# STM32L412CBU6.net
KiCad netlist of a schematic drawn in Altium Designer
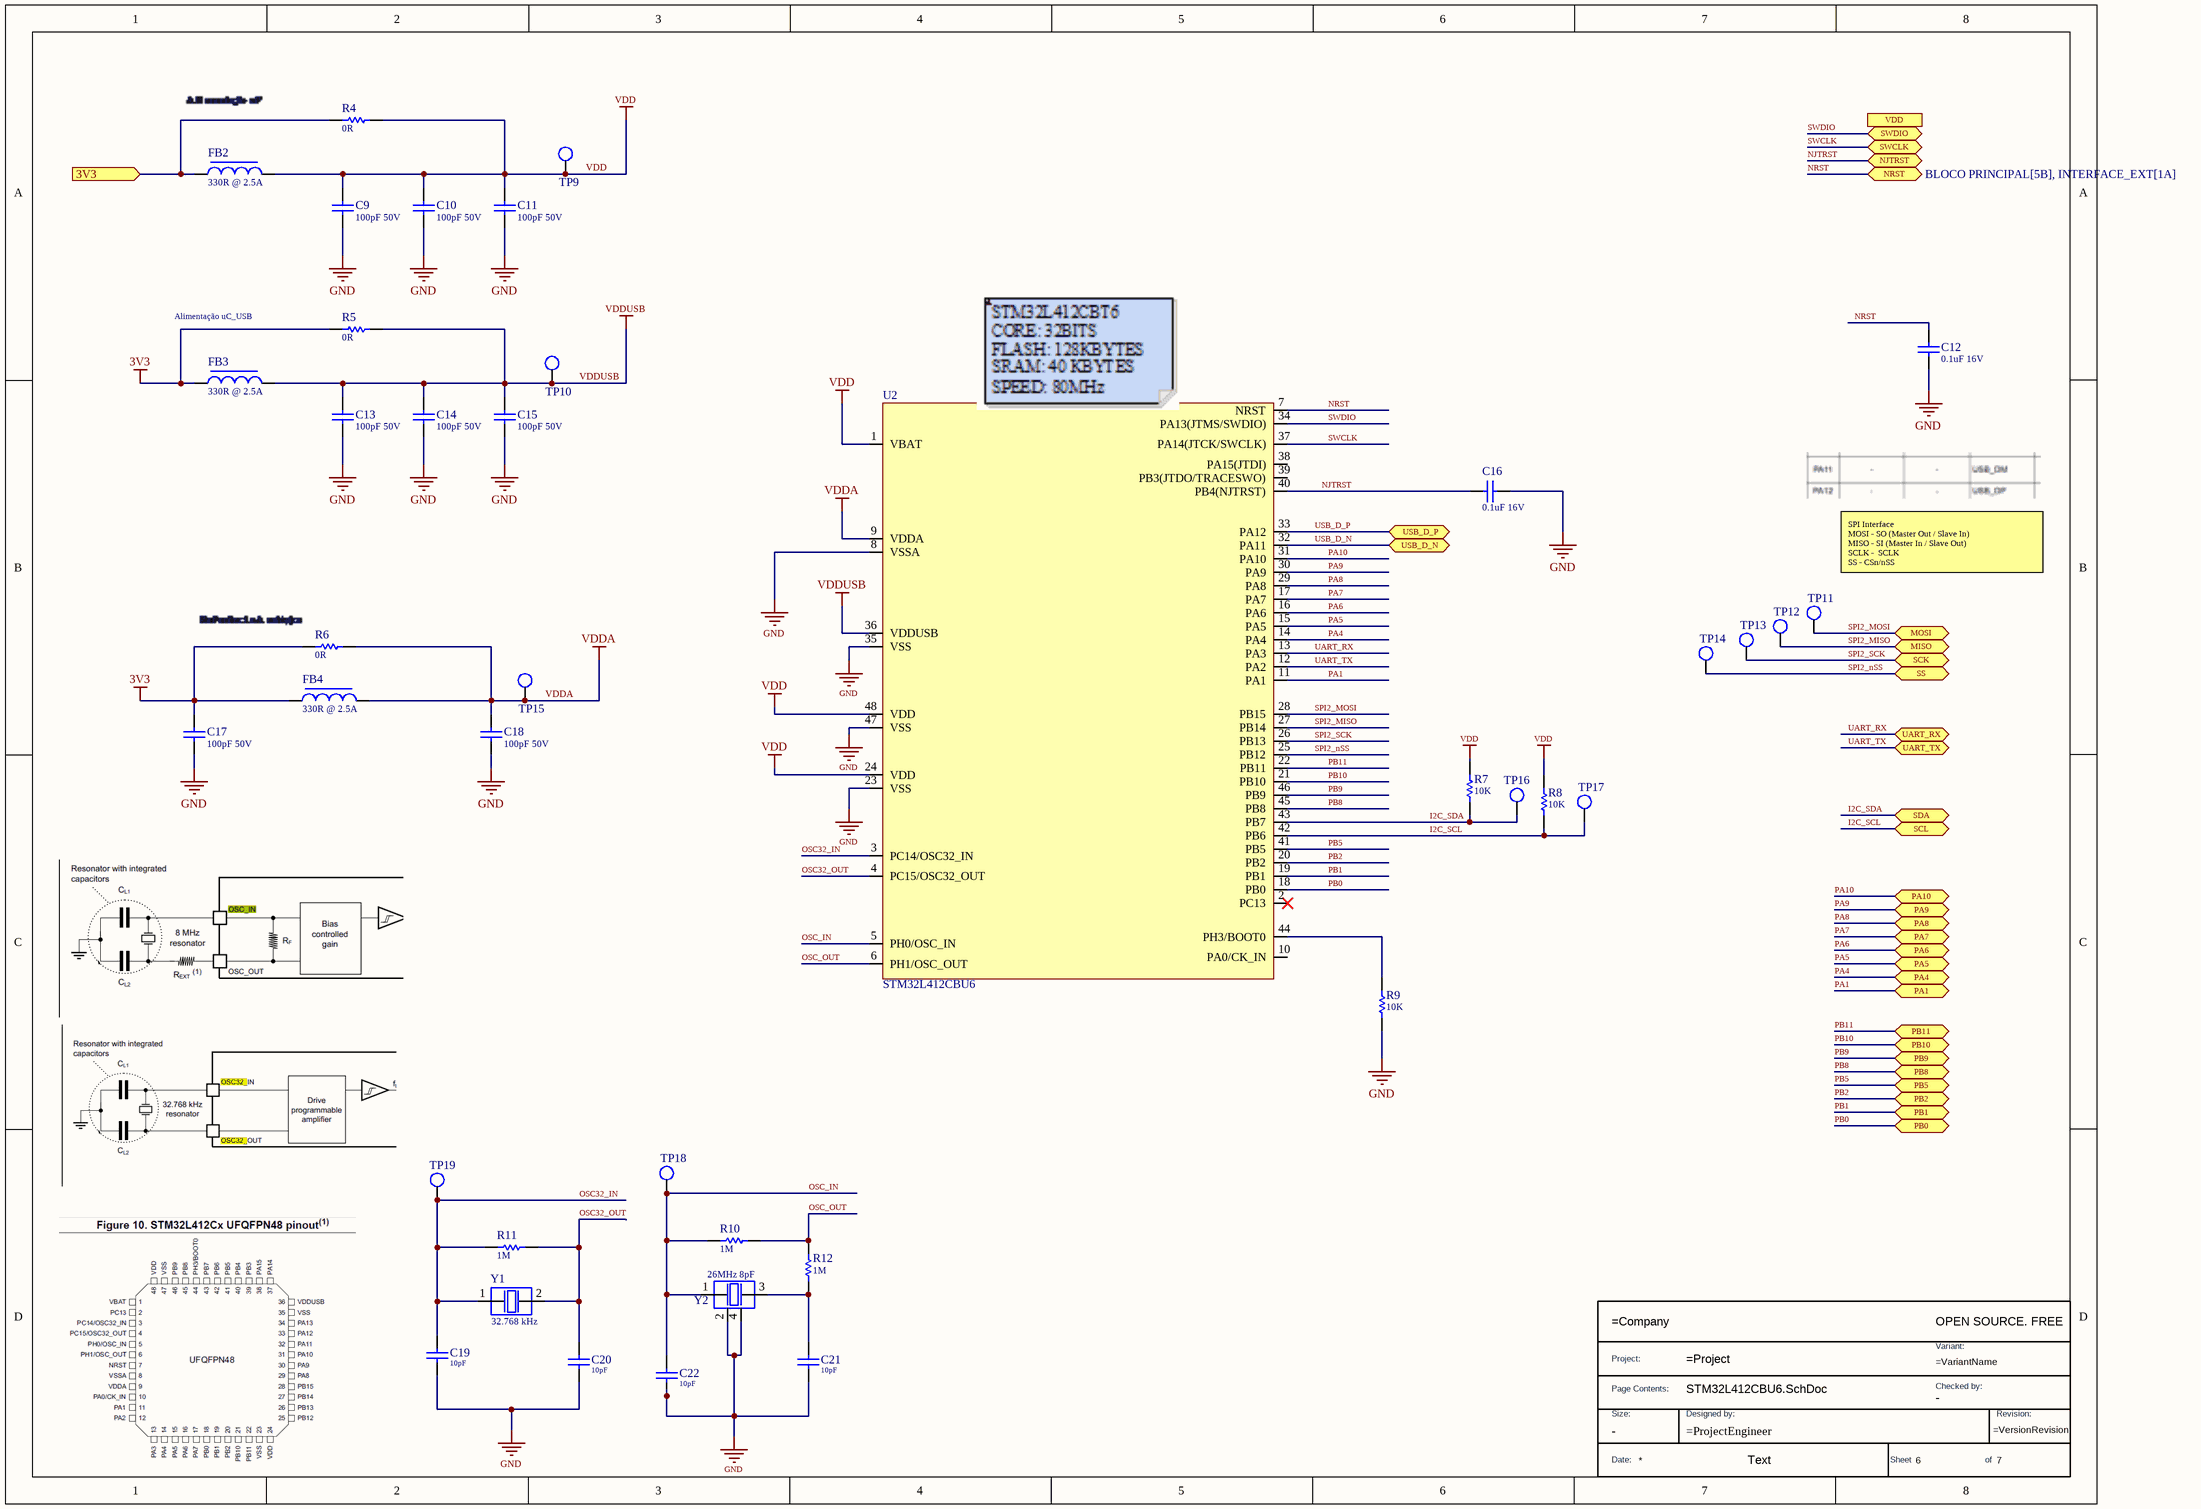
[diagram p0: STM32L412CBU6.SchDoc]

(export (version "E")
  (design (tool "Eeschema 10.0.6"))
  (components
    (comp (ref "C9")
      (value "CC0805JRNPO9BN101")
      (footprint "CAP_0805")
      (description "CAP CER 100PF 50V C0G/NPO 0805")
      (fields (field (name "MANUFACTURER") "YAGEO") (field (name "VALOR") "100pF 50V"))
      (libsource (lib "OBDH_Ed02") (part "CC0805JRNPO9BN101"))
    )
    (comp (ref "C10")
      (value "CC0805JRNPO9BN101")
      (footprint "CAP_0805")
      (description "CAP CER 100PF 50V C0G/NPO 0805")
      (fields (field (name "MANUFACTURER") "YAGEO") (field (name "VALOR") "100pF 50V"))
      (libsource (lib "OBDH_Ed02") (part "CC0805JRNPO9BN101"))
    )
    (comp (ref "C11")
      (value "CC0805JRNPO9BN101")
      (footprint "CAP_0805")
      (description "CAP CER 100PF 50V C0G/NPO 0805")
      (fields (field (name "MANUFACTURER") "YAGEO") (field (name "VALOR") "100pF 50V"))
      (libsource (lib "OBDH_Ed02") (part "CC0805JRNPO9BN101"))
    )
    (comp (ref "C12")
      (value "CL05B104KO5NNNC")
      (footprint "CAP_0805")
      (description "CAP CER 0.1UF 16V X5R 0805")
      (fields (field (name "MANUFACTURER") "Samsung Electro-Mechanics") (field (name "VALOR") "0.1uF 16V"))
      (libsource (lib "OBDH_Ed02") (part "CL05B104KO5NNNC"))
    )
    (comp (ref "C13")
      (value "CC0805JRNPO9BN101")
      (footprint "CAP_0805")
      (description "CAP CER 100PF 50V C0G/NPO 0805")
      (fields (field (name "MANUFACTURER") "YAGEO") (field (name "VALOR") "100pF 50V"))
      (libsource (lib "OBDH_Ed02") (part "CC0805JRNPO9BN101"))
    )
    (comp (ref "C14")
      (value "CC0805JRNPO9BN101")
      (footprint "CAP_0805")
      (description "CAP CER 100PF 50V C0G/NPO 0805")
      (fields (field (name "MANUFACTURER") "YAGEO") (field (name "VALOR") "100pF 50V"))
      (libsource (lib "OBDH_Ed02") (part "CC0805JRNPO9BN101"))
    )
    (comp (ref "C15")
      (value "CC0805JRNPO9BN101")
      (footprint "CAP_0805")
      (description "CAP CER 100PF 50V C0G/NPO 0805")
      (fields (field (name "MANUFACTURER") "YAGEO") (field (name "VALOR") "100pF 50V"))
      (libsource (lib "OBDH_Ed02") (part "CC0805JRNPO9BN101"))
    )
    (comp (ref "C16")
      (value "CL05B104KO5NNNC")
      (footprint "CAP_0805")
      (description "CAP CER 0.1UF 16V X5R 0805")
      (fields (field (name "MANUFACTURER") "Samsung Electro-Mechanics") (field (name "VALOR") "0.1uF 16V"))
      (libsource (lib "OBDH_Ed02") (part "CL05B104KO5NNNC"))
    )
    (comp (ref "C17")
      (value "CC0805JRNPO9BN101")
      (footprint "CAP_0805")
      (description "CAP CER 100PF 50V C0G/NPO 0805")
      (fields (field (name "MANUFACTURER") "YAGEO") (field (name "VALOR") "100pF 50V"))
      (libsource (lib "OBDH_Ed02") (part "CC0805JRNPO9BN101"))
    )
    (comp (ref "C18")
      (value "CC0805JRNPO9BN101")
      (footprint "CAP_0805")
      (description "CAP CER 100PF 50V C0G/NPO 0805")
      (fields (field (name "MANUFACTURER") "YAGEO") (field (name "VALOR") "100pF 50V"))
      (libsource (lib "OBDH_Ed02") (part "CC0805JRNPO9BN101"))
    )
    (comp (ref "C19")
      (value "GRM1555C1H100FA01D")
      (footprint "CAP 0402")
      (description "CAP CER 10PF 50V C0G/NP0 0402")
      (fields (field (name "MANUFACTURER") "Murata Electronics") (field (name "VALOR") "10pF"))
      (libsource (lib "OBDH_Ed02") (part "GRM1555C1H100FA01D"))
    )
    (comp (ref "C20")
      (value "GRM1555C1H100FA01D")
      (footprint "CAP 0402")
      (description "CAP CER 10PF 50V C0G/NP0 0402")
      (fields (field (name "MANUFACTURER") "Murata Electronics") (field (name "VALOR") "10pF"))
      (libsource (lib "OBDH_Ed02") (part "GRM1555C1H100FA01D"))
    )
    (comp (ref "C21")
      (value "GRM1555C1H100FA01D")
      (footprint "CAP 0402")
      (description "CAP CER 10PF 50V C0G/NP0 0402")
      (fields (field (name "MANUFACTURER") "Murata Electronics") (field (name "VALOR") "10pF"))
      (libsource (lib "OBDH_Ed02") (part "GRM1555C1H100FA01D"))
    )
    (comp (ref "C22")
      (value "GRM1555C1H100FA01D")
      (footprint "CAP 0402")
      (description "CAP CER 10PF 50V C0G/NP0 0402")
      (fields (field (name "MANUFACTURER") "Murata Electronics") (field (name "VALOR") "10pF"))
      (libsource (lib "OBDH_Ed02") (part "GRM1555C1H100FA01D"))
    )
    (comp (ref "FB2")
      (value "MPZ2012S331AT000")
      (footprint "IND_0805")
      (description "FERRITE BEAD 330 OHM 0805 1LN")
      (fields (field (name "MANUFACTURER") "TDK Corporation") (field (name "VALOR") "330R @ 2.5A"))
      (libsource (lib "OBDH_Ed02") (part "MPZ2012S331AT000"))
    )
    (comp (ref "FB3")
      (value "MPZ2012S331AT000")
      (footprint "IND_0805")
      (description "FERRITE BEAD 330 OHM 0805 1LN")
      (fields (field (name "MANUFACTURER") "TDK Corporation") (field (name "VALOR") "330R @ 2.5A"))
      (libsource (lib "OBDH_Ed02") (part "MPZ2012S331AT000"))
    )
    (comp (ref "FB4")
      (value "MPZ2012S331AT000")
      (footprint "IND_0805")
      (description "FERRITE BEAD 330 OHM 0805 1LN")
      (fields (field (name "MANUFACTURER") "TDK Corporation") (field (name "VALOR") "330R @ 2.5A"))
      (libsource (lib "OBDH_Ed02") (part "MPZ2012S331AT000"))
    )
    (comp (ref "R4")
      (value "RC0805JR-070RL")
      (footprint "RES_0805")
      (description "RES 0 OHM JUMPER 1/8W 0805")
      (fields (field (name "MANUFACTURER") "YAGEO") (field (name "VALOR") "0R"))
      (libsource (lib "OBDH_Ed02") (part "RC0805JR-070RL"))
    )
    (comp (ref "R5")
      (value "RC0805JR-070RL")
      (footprint "RES_0805")
      (description "RES 0 OHM JUMPER 1/8W 0805")
      (fields (field (name "MANUFACTURER") "YAGEO") (field (name "VALOR") "0R"))
      (libsource (lib "OBDH_Ed02") (part "RC0805JR-070RL"))
    )
    (comp (ref "R6")
      (value "RC0805JR-070RL")
      (footprint "RES_0805")
      (description "RES 0 OHM JUMPER 1/8W 0805")
      (fields (field (name "MANUFACTURER") "YAGEO") (field (name "VALOR") "0R"))
      (libsource (lib "OBDH_Ed02") (part "RC0805JR-070RL"))
    )
    (comp (ref "R7")
      (value "AF0805JR-0710KL")
      (footprint "RES_0805")
      (description "RES SMD 10K OHM 5% 1/8W 0805")
      (fields (field (name "MANUFACTURER") "YAGEO") (field (name "VALOR") "10K"))
      (libsource (lib "OBDH_Ed02") (part "AF0805JR-0710KL"))
    )
    (comp (ref "R8")
      (value "AF0805JR-0710KL")
      (footprint "RES_0805")
      (description "RES SMD 10K OHM 5% 1/8W 0805")
      (fields (field (name "MANUFACTURER") "YAGEO") (field (name "VALOR") "10K"))
      (libsource (lib "OBDH_Ed02") (part "AF0805JR-0710KL"))
    )
    (comp (ref "R9")
      (value "AF0805JR-0710KL")
      (footprint "RES_0805")
      (description "RES SMD 10K OHM 5% 1/8W 0805")
      (fields (field (name "MANUFACTURER") "YAGEO") (field (name "VALOR") "10K"))
      (libsource (lib "OBDH_Ed02") (part "AF0805JR-0710KL"))
    )
    (comp (ref "R10")
      (value "CRCW08051M00JNEA")
      (footprint "RES 0402")
      (description "RES SMD 1M OHM 5% 1/8W 0805")
      (fields (field (name "MANUFACTURER") "Vishay Intertech") (field (name "VALOR") "1M"))
      (libsource (lib "OBDH_Ed02") (part "CRCW08051M00JNEA"))
    )
    (comp (ref "R11")
      (value "CRCW08051M00JNEA")
      (footprint "RES 0402")
      (description "RES SMD 1M OHM 5% 1/8W 0805")
      (fields (field (name "MANUFACTURER") "Vishay Intertech") (field (name "VALOR") "1M"))
      (libsource (lib "OBDH_Ed02") (part "CRCW08051M00JNEA"))
    )
    (comp (ref "R12")
      (value "CRCW08051M00JNEA")
      (footprint "RES 0402")
      (description "RES SMD 1M OHM 5% 1/8W 0805")
      (fields (field (name "MANUFACTURER") "Vishay Intertech") (field (name "VALOR") "1M"))
      (libsource (lib "OBDH_Ed02") (part "CRCW08051M00JNEA"))
    )
    (comp (ref "TP9")
      (value "TEST_POINT_1.5MM")
      (footprint "TESTPOINT_1.5MM")
      (description "TEST_POINT")
      (libsource (lib "OBDH_Ed02") (part "TEST_POINT_1.5MM"))
    )
    (comp (ref "TP10")
      (value "TEST_POINT_1.5MM")
      (footprint "TESTPOINT_1.5MM")
      (description "TEST_POINT")
      (libsource (lib "OBDH_Ed02") (part "TEST_POINT_1.5MM"))
    )
    (comp (ref "TP11")
      (value "TEST_POINT_1.5MM")
      (footprint "TESTPOINT_1.5MM")
      (description "TEST_POINT")
      (libsource (lib "OBDH_Ed02") (part "TEST_POINT_1.5MM"))
    )
    (comp (ref "TP12")
      (value "TEST_POINT_1.5MM")
      (footprint "TESTPOINT_1.5MM")
      (description "TEST_POINT")
      (libsource (lib "OBDH_Ed02") (part "TEST_POINT_1.5MM"))
    )
    (comp (ref "TP13")
      (value "TEST_POINT_1.5MM")
      (footprint "TESTPOINT_1.5MM")
      (description "TEST_POINT")
      (libsource (lib "OBDH_Ed02") (part "TEST_POINT_1.5MM"))
    )
    (comp (ref "TP14")
      (value "TEST_POINT_1.5MM")
      (footprint "TESTPOINT_1.5MM")
      (description "TEST_POINT")
      (libsource (lib "OBDH_Ed02") (part "TEST_POINT_1.5MM"))
    )
    (comp (ref "TP15")
      (value "TEST_POINT_1.5MM")
      (footprint "TESTPOINT_1.5MM")
      (description "TEST_POINT")
      (libsource (lib "OBDH_Ed02") (part "TEST_POINT_1.5MM"))
    )
    (comp (ref "TP16")
      (value "TEST_POINT_1.5MM")
      (footprint "TESTPOINT_1.5MM")
      (description "TEST_POINT")
      (libsource (lib "OBDH_Ed02") (part "TEST_POINT_1.5MM"))
    )
    (comp (ref "TP17")
      (value "TEST_POINT_1.5MM")
      (footprint "TESTPOINT_1.5MM")
      (description "TEST_POINT")
      (libsource (lib "OBDH_Ed02") (part "TEST_POINT_1.5MM"))
    )
    (comp (ref "TP18")
      (value "TEST_POINT_1.5MM")
      (footprint "TESTPOINT_1.5MM")
      (description "TEST_POINT")
      (libsource (lib "OBDH_Ed02") (part "TEST_POINT_1.5MM"))
    )
    (comp (ref "TP19")
      (value "TEST_POINT_1.5MM")
      (footprint "TESTPOINT_1.5MM")
      (description "TEST_POINT")
      (libsource (lib "OBDH_Ed02") (part "TEST_POINT_1.5MM"))
    )
    (comp (ref "U2")
      (value "STM32L412CBU6")
      (footprint "QFN-48")
      (libsource (lib "OBDH_Ed02") (part "STM32L412CBU6"))
    )
    (comp (ref "Y1")
      (value "ABS07-32.768KHZ-7-T")
      (footprint "Crystal_32k")
      (description "CRYSTAL 32.7680KHZ 7PF SMD")
      (fields (field (name "MANUFACTURER") "Abracon LLC") (field (name "VALOR") "32.768 kHz"))
      (libsource (lib "OBDH_Ed02") (part "ABS07-32.768KHZ-7-T"))
    )
    (comp (ref "Y2")
      (value "NX3225SA-26MHZ")
      (footprint "Crystal-4SMD")
      (description "CRYSTAL 26.0000MHZ 10PF SMD")
      (fields (field (name "MANUFACTURER") "NDK America, Inc.") (field (name "VALOR") "26MHz 8pF"))
      (libsource (lib "OBDH_Ed02") (part "NX3225SA-26MHZ"))
    )
  )
  (nets
    (net (code "1") (name "/I2C_SCL") (class "Default")
      (node (ref "R8") (pin "1") (pinfunction "1_1") (pintype "passive"))
      (node (ref "TP17") (pin "1") (pinfunction "1_1") (pintype "passive"))
      (node (ref "U2") (pin "42") (pinfunction "PB6_42") (pintype "bidirectional"))
    )
    (net (code "2") (name "/I2C_SDA") (class "Default")
      (node (ref "R7") (pin "1") (pinfunction "1_1") (pintype "passive"))
      (node (ref "TP16") (pin "1") (pinfunction "1_1") (pintype "passive"))
      (node (ref "U2") (pin "43") (pinfunction "PB7_43") (pintype "bidirectional"))
    )
    (net (code "3") (name "/NJTRST") (class "Default")
      (node (ref "C16") (pin "1") (pinfunction "1_1") (pintype "passive"))
      (node (ref "U2") (pin "40") (pinfunction "PB4(NJTRST)_40") (pintype "bidirectional"))
    )
    (net (code "4") (name "/NRST") (class "Default")
      (node (ref "C12") (pin "2") (pinfunction "2_2") (pintype "passive"))
      (node (ref "U2") (pin "7") (pinfunction "NRST_7") (pintype "bidirectional"))
    )
    (net (code "5") (name "/OSC32_IN") (class "Default")
      (node (ref "C19") (pin "2") (pinfunction "2_2") (pintype "passive"))
      (node (ref "R11") (pin "1") (pinfunction "1_1") (pintype "passive"))
      (node (ref "TP19") (pin "1") (pinfunction "1_1") (pintype "passive"))
      (node (ref "U2") (pin "3") (pinfunction "PC14/OSC32_IN_3") (pintype "bidirectional"))
      (node (ref "Y1") (pin "1") (pinfunction "1_1") (pintype "passive"))
    )
    (net (code "6") (name "/OSC32_OUT") (class "Default")
      (node (ref "C20") (pin "2") (pinfunction "2_2") (pintype "passive"))
      (node (ref "R11") (pin "2") (pinfunction "2_2") (pintype "passive"))
      (node (ref "U2") (pin "4") (pinfunction "PC15/OSC32_OUT_4") (pintype "bidirectional"))
      (node (ref "Y1") (pin "2") (pinfunction "2_2") (pintype "passive"))
    )
    (net (code "7") (name "/OSC_IN") (class "Default")
      (node (ref "C22") (pin "2") (pinfunction "2_2") (pintype "passive"))
      (node (ref "R10") (pin "1") (pinfunction "1_1") (pintype "passive"))
      (node (ref "TP18") (pin "1") (pinfunction "1_1") (pintype "passive"))
      (node (ref "U2") (pin "5") (pinfunction "PH0/OSC_IN_5") (pintype "bidirectional"))
      (node (ref "Y2") (pin "1") (pinfunction "1_1") (pintype "passive"))
    )
    (net (code "8") (name "/OSC_OUT") (class "Default")
      (node (ref "R10") (pin "2") (pinfunction "2_2") (pintype "passive"))
      (node (ref "R12") (pin "2") (pinfunction "2_2") (pintype "passive"))
      (node (ref "U2") (pin "6") (pinfunction "PH1/OSC_OUT_6") (pintype "bidirectional"))
    )
    (net (code "9") (name "/PA1") (class "Default")
      (node (ref "U2") (pin "11") (pinfunction "PA1_11") (pintype "bidirectional"))
    )
    (net (code "10") (name "/PA4") (class "Default")
      (node (ref "U2") (pin "14") (pinfunction "PA4_14") (pintype "bidirectional"))
    )
    (net (code "11") (name "/PA5") (class "Default")
      (node (ref "U2") (pin "15") (pinfunction "PA5_15") (pintype "bidirectional"))
    )
    (net (code "12") (name "/PA6") (class "Default")
      (node (ref "U2") (pin "16") (pinfunction "PA6_16") (pintype "bidirectional"))
    )
    (net (code "13") (name "/PA7") (class "Default")
      (node (ref "U2") (pin "17") (pinfunction "PA7_17") (pintype "bidirectional"))
    )
    (net (code "14") (name "/PA8") (class "Default")
      (node (ref "U2") (pin "29") (pinfunction "PA8_29") (pintype "bidirectional"))
    )
    (net (code "15") (name "/PA9") (class "Default")
      (node (ref "U2") (pin "30") (pinfunction "PA9_30") (pintype "bidirectional"))
    )
    (net (code "16") (name "/PA10") (class "Default")
      (node (ref "U2") (pin "31") (pinfunction "PA10_31") (pintype "bidirectional"))
    )
    (net (code "17") (name "/PB0") (class "Default")
      (node (ref "U2") (pin "18") (pinfunction "PB0_18") (pintype "bidirectional"))
    )
    (net (code "18") (name "/PB1") (class "Default")
      (node (ref "U2") (pin "19") (pinfunction "PB1_19") (pintype "bidirectional"))
    )
    (net (code "19") (name "/PB2") (class "Default")
      (node (ref "U2") (pin "20") (pinfunction "PB2_20") (pintype "bidirectional"))
    )
    (net (code "20") (name "/PB5") (class "Default")
      (node (ref "U2") (pin "41") (pinfunction "PB5_41") (pintype "bidirectional"))
    )
    (net (code "21") (name "/PB8") (class "Default")
      (node (ref "U2") (pin "45") (pinfunction "PB8_45") (pintype "bidirectional"))
    )
    (net (code "22") (name "/PB9") (class "Default")
      (node (ref "U2") (pin "46") (pinfunction "PB9_46") (pintype "bidirectional"))
    )
    (net (code "23") (name "/PB10") (class "Default")
      (node (ref "U2") (pin "21") (pinfunction "PB10_21") (pintype "bidirectional"))
    )
    (net (code "24") (name "/PB11") (class "Default")
      (node (ref "U2") (pin "22") (pinfunction "PB11_22") (pintype "bidirectional"))
    )
    (net (code "25") (name "/SPI2_MISO") (class "Default")
      (node (ref "TP12") (pin "1") (pinfunction "1_1") (pintype "passive"))
      (node (ref "U2") (pin "27") (pinfunction "PB14_27") (pintype "bidirectional"))
    )
    (net (code "26") (name "/SPI2_MOSI") (class "Default")
      (node (ref "TP11") (pin "1") (pinfunction "1_1") (pintype "passive"))
      (node (ref "U2") (pin "28") (pinfunction "PB15_28") (pintype "bidirectional"))
    )
    (net (code "27") (name "/SPI2_SCK") (class "Default")
      (node (ref "TP13") (pin "1") (pinfunction "1_1") (pintype "passive"))
      (node (ref "U2") (pin "26") (pinfunction "PB13_26") (pintype "bidirectional"))
    )
    (net (code "28") (name "/SPI2_nSS") (class "Default")
      (node (ref "TP14") (pin "1") (pinfunction "1_1") (pintype "passive"))
      (node (ref "U2") (pin "25") (pinfunction "PB12_25") (pintype "bidirectional"))
    )
    (net (code "29") (name "/SWCLK") (class "Default")
      (node (ref "U2") (pin "37") (pinfunction "PA14(JTCK/SWCLK)_37") (pintype "bidirectional"))
    )
    (net (code "30") (name "/SWDIO") (class "Default")
      (node (ref "U2") (pin "34") (pinfunction "PA13(JTMS/SWDIO)_34") (pintype "bidirectional"))
    )
    (net (code "31") (name "/UART_RX") (class "Default")
      (node (ref "U2") (pin "13") (pinfunction "PA3_13") (pintype "bidirectional"))
    )
    (net (code "32") (name "/UART_TX") (class "Default")
      (node (ref "U2") (pin "12") (pinfunction "PA2_12") (pintype "bidirectional"))
    )
    (net (code "33") (name "/USB_D_N") (class "Default")
      (node (ref "U2") (pin "32") (pinfunction "PA11_32") (pintype "bidirectional"))
    )
    (net (code "34") (name "/USB_D_P") (class "Default")
      (node (ref "U2") (pin "33") (pinfunction "PA12_33") (pintype "bidirectional"))
    )
    (net (code "35") (name "3V3") (class "Default")
      (node (ref "C17") (pin "2") (pinfunction "2_2") (pintype "passive"))
      (node (ref "FB2") (pin "1") (pinfunction "1_1") (pintype "passive"))
      (node (ref "FB3") (pin "1") (pinfunction "1_1") (pintype "passive"))
      (node (ref "FB4") (pin "1") (pinfunction "1_1") (pintype "passive"))
      (node (ref "R4") (pin "1") (pinfunction "1_1") (pintype "passive"))
      (node (ref "R5") (pin "1") (pinfunction "1_1") (pintype "passive"))
      (node (ref "R6") (pin "1") (pinfunction "1_1") (pintype "passive"))
    )
    (net (code "36") (name "GND") (class "Default")
      (node (ref "C10") (pin "1") (pinfunction "1_1") (pintype "passive"))
      (node (ref "C11") (pin "1") (pinfunction "1_1") (pintype "passive"))
      (node (ref "C12") (pin "1") (pinfunction "1_1") (pintype "passive"))
      (node (ref "C13") (pin "1") (pinfunction "1_1") (pintype "passive"))
      (node (ref "C14") (pin "1") (pinfunction "1_1") (pintype "passive"))
      (node (ref "C15") (pin "1") (pinfunction "1_1") (pintype "passive"))
      (node (ref "C16") (pin "2") (pinfunction "2_2") (pintype "passive"))
      (node (ref "C17") (pin "1") (pinfunction "1_1") (pintype "passive"))
      (node (ref "C18") (pin "1") (pinfunction "1_1") (pintype "passive"))
      (node (ref "C19") (pin "1") (pinfunction "1_1") (pintype "passive"))
      (node (ref "C20") (pin "1") (pinfunction "1_1") (pintype "passive"))
      (node (ref "C21") (pin "1") (pinfunction "1_1") (pintype "passive"))
      (node (ref "C22") (pin "1") (pinfunction "1_1") (pintype "passive"))
      (node (ref "C9") (pin "1") (pinfunction "1_1") (pintype "passive"))
      (node (ref "R9") (pin "1") (pinfunction "1_1") (pintype "passive"))
      (node (ref "U2") (pin "23") (pinfunction "VSS_23") (pintype "power_in"))
      (node (ref "U2") (pin "35") (pinfunction "VSS_35") (pintype "passive"))
      (node (ref "U2") (pin "47") (pinfunction "VSS_47") (pintype "power_in"))
      (node (ref "U2") (pin "8") (pinfunction "VSSA_8") (pintype "passive"))
      (node (ref "Y2") (pin "2") (pinfunction "2_2") (pintype "passive"))
      (node (ref "Y2") (pin "4") (pinfunction "4_4") (pintype "passive"))
    )
    (net (code "37") (name "Net-(C21-Pad2)") (class "Default")
      (node (ref "C21") (pin "2") (pinfunction "2_2") (pintype "passive"))
      (node (ref "R12") (pin "1") (pinfunction "1_1") (pintype "passive"))
      (node (ref "Y2") (pin "3") (pinfunction "3_3") (pintype "passive"))
    )
    (net (code "38") (name "Net-(U2-PH3{slash}BOOT0)") (class "Default")
      (node (ref "R9") (pin "2") (pinfunction "2_2") (pintype "passive"))
      (node (ref "U2") (pin "44") (pinfunction "PH3/BOOT0_44") (pintype "bidirectional"))
    )
    (net (code "39") (name "VDD") (class "Default")
      (node (ref "C10") (pin "2") (pinfunction "2_2") (pintype "passive"))
      (node (ref "C11") (pin "2") (pinfunction "2_2") (pintype "passive"))
      (node (ref "C9") (pin "2") (pinfunction "2_2") (pintype "passive"))
      (node (ref "FB2") (pin "2") (pinfunction "2_2") (pintype "passive"))
      (node (ref "R4") (pin "2") (pinfunction "2_2") (pintype "passive"))
      (node (ref "R7") (pin "2") (pinfunction "2_2") (pintype "passive"))
      (node (ref "R8") (pin "2") (pinfunction "2_2") (pintype "passive"))
      (node (ref "TP9") (pin "1") (pinfunction "1_1") (pintype "passive"))
      (node (ref "U2") (pin "1") (pinfunction "VBAT_1") (pintype "power_in"))
      (node (ref "U2") (pin "24") (pinfunction "VDD_24") (pintype "power_in"))
      (node (ref "U2") (pin "48") (pinfunction "VDD_48") (pintype "power_in"))
    )
    (net (code "40") (name "VDDA") (class "Default")
      (node (ref "C18") (pin "2") (pinfunction "2_2") (pintype "passive"))
      (node (ref "FB4") (pin "2") (pinfunction "2_2") (pintype "passive"))
      (node (ref "R6") (pin "2") (pinfunction "2_2") (pintype "passive"))
      (node (ref "TP15") (pin "1") (pinfunction "1_1") (pintype "passive"))
      (node (ref "U2") (pin "9") (pinfunction "VDDA_9") (pintype "power_in"))
    )
    (net (code "41") (name "VDDUSB") (class "Default")
      (node (ref "C13") (pin "2") (pinfunction "2_2") (pintype "passive"))
      (node (ref "C14") (pin "2") (pinfunction "2_2") (pintype "passive"))
      (node (ref "C15") (pin "2") (pinfunction "2_2") (pintype "passive"))
      (node (ref "FB3") (pin "2") (pinfunction "2_2") (pintype "passive"))
      (node (ref "R5") (pin "2") (pinfunction "2_2") (pintype "passive"))
      (node (ref "TP10") (pin "1") (pinfunction "1_1") (pintype "passive"))
      (node (ref "U2") (pin "36") (pinfunction "VDDUSB_36") (pintype "power_in"))
    )
    (net (code "42") (name "unconnected-(U2-PA0{slash}CK_IN-Pad10)") (class "Default")
      (node (ref "U2") (pin "10") (pinfunction "PA0/CK_IN_10") (pintype "bidirectional"))
    )
    (net (code "43") (name "unconnected-(U2-PA15(JTDI)-Pad38)") (class "Default")
      (node (ref "U2") (pin "38") (pinfunction "PA15(JTDI)_38") (pintype "bidirectional"))
    )
    (net (code "44") (name "unconnected-(U2-PB3(JTDO{slash}TRACESWO)-Pad39)") (class "Default")
      (node (ref "U2") (pin "39") (pinfunction "PB3(JTDO/TRACESWO)_39") (pintype "bidirectional"))
    )
    (net (code "45") (name "unconnected-(U2-PC13-Pad2)") (class "Default")
      (node (ref "U2") (pin "2") (pinfunction "PC13_2") (pintype "bidirectional+no_connect"))
    )
  )
)
